# motor.net
KiCad netlist of a schematic drawn in EAGLE
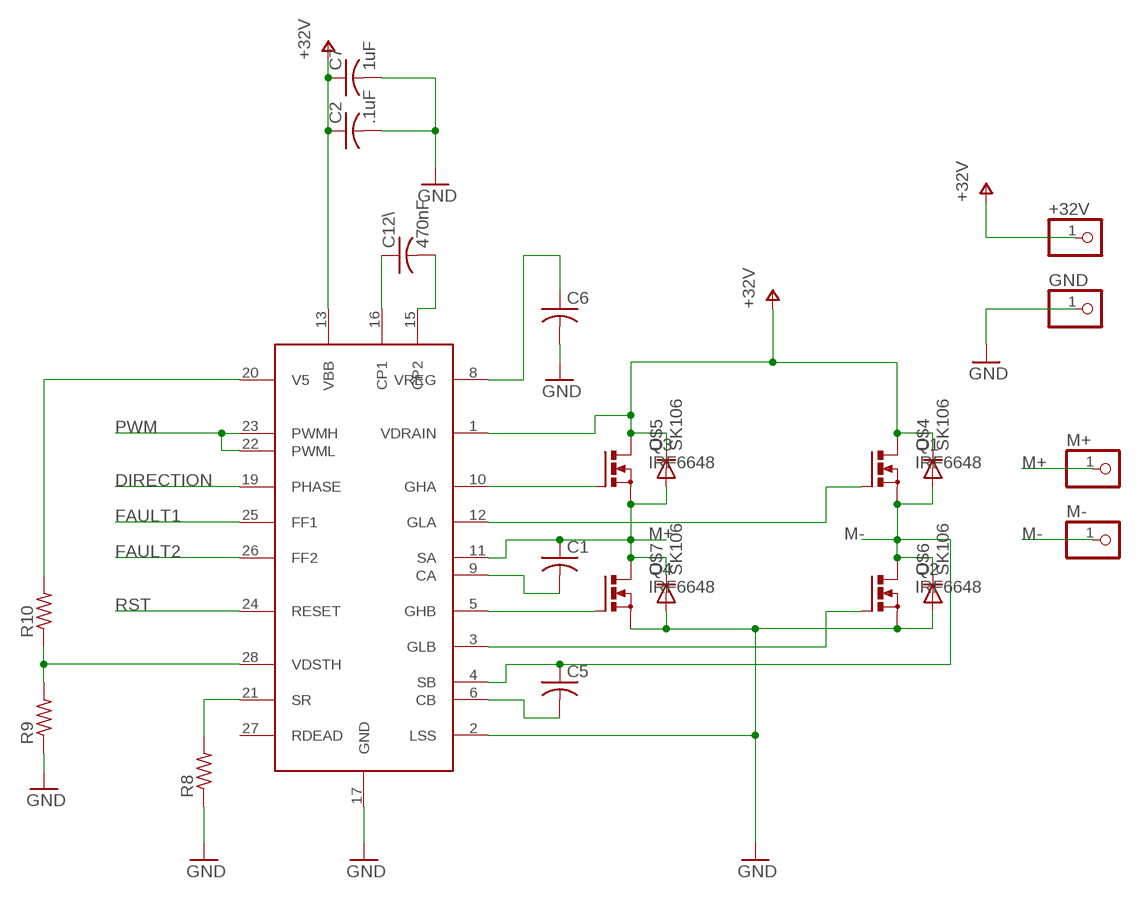
[diagram p0: schematic, sheet 1]
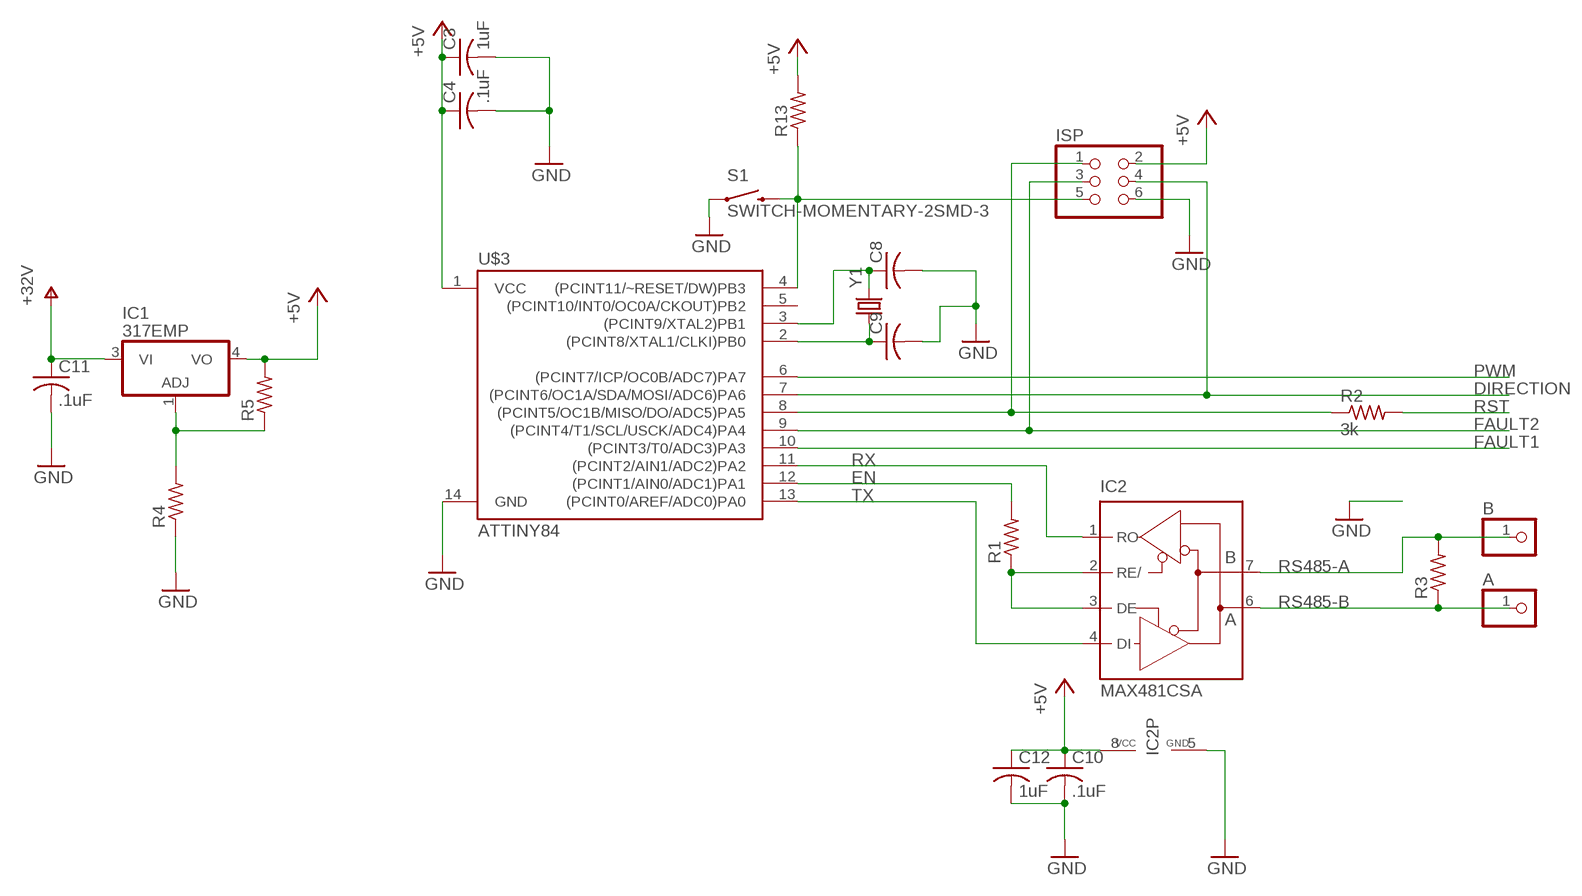
[diagram p1: schematic, sheet 2]

(export (version "E")
  (design (tool "Eeschema 10.0.6"))
  (components
    (comp (ref "A")
      (value "PINHD-1X1")
      (footprint "eagle-import:1X01")
      (libsource (lib "eagle-import") (part "PINHD-1X1"))
    )
    (comp (ref "B")
      (value "PINHD-1X1")
      (footprint "eagle-import:1X01")
      (libsource (lib "eagle-import") (part "PINHD-1X1"))
    )
    (comp (ref "C3")
      (value "1uF")
      (footprint "eagle-import:C0603")
      (libsource (lib "eagle-import") (part "C-USC0603"))
    )
    (comp (ref "C4")
      (value ".1uF")
      (footprint "eagle-import:C0603")
      (libsource (lib "eagle-import") (part "C-USC0603"))
    )
    (comp (ref "C8")
      (value "C-USC0603")
      (footprint "eagle-import:C0603")
      (libsource (lib "eagle-import") (part "C-USC0603"))
    )
    (comp (ref "C9")
      (value "C-USC0603")
      (footprint "eagle-import:C0603")
      (libsource (lib "eagle-import") (part "C-USC0603"))
    )
    (comp (ref "C10")
      (value ".1uF")
      (footprint "eagle-import:C0603")
      (libsource (lib "eagle-import") (part "C-USC0603"))
    )
    (comp (ref "C11")
      (value ".1uF")
      (footprint "eagle-import:C0603")
      (libsource (lib "eagle-import") (part "C-USC0603"))
    )
    (comp (ref "C12")
      (value "1uF")
      (footprint "eagle-import:C0603")
      (libsource (lib "eagle-import") (part "C-USC0603"))
    )
    (comp (ref "IC1")
      (value "317EMP")
      (footprint "eagle-import:SOT223")
      (libsource (lib "eagle-import") (part "317EMP"))
    )
    (comp (ref "IC2")
      (value "MAX481CSA")
      (footprint "eagle-import:SO08")
      (fields (field (name "MF") "MAXIM"))
      (libsource (lib "eagle-import") (part "MAX481CSA"))
    )
    (comp (ref "ISP")
      (value "PINHD-2X3")
      (footprint "eagle-import:2X03")
      (libsource (lib "eagle-import") (part "PINHD-2X3"))
    )
    (comp (ref "R1")
      (value "R-US_R0603")
      (footprint "eagle-import:R0603")
      (libsource (lib "eagle-import") (part "R-US_R0603"))
    )
    (comp (ref "R2")
      (value "3k")
      (footprint "eagle-import:R0603")
      (libsource (lib "eagle-import") (part "R-US_R0603"))
    )
    (comp (ref "R3")
      (value "R-US_R0603")
      (footprint "eagle-import:R0603")
      (libsource (lib "eagle-import") (part "R-US_R0603"))
    )
    (comp (ref "R4")
      (value "R-US_R0603")
      (footprint "eagle-import:R0603")
      (libsource (lib "eagle-import") (part "R-US_R0603"))
    )
    (comp (ref "R5")
      (value "R-US_R0603")
      (footprint "eagle-import:R0603")
      (libsource (lib "eagle-import") (part "R-US_R0603"))
    )
    (comp (ref "R13")
      (value "R-US_R0603")
      (footprint "eagle-import:R0603")
      (libsource (lib "eagle-import") (part "R-US_R0603"))
    )
    (comp (ref "S1")
      (value "SWITCH-MOMENTARY-2SMD-3")
      (footprint "eagle-import:TACTILE_SWITCH_SMD-3")
      (libsource (lib "eagle-import") (part "SWITCH-MOMENTARY-2SMD-3"))
    )
    (comp (ref "U$3")
      (value "ATTINY84")
      (footprint "eagle-import:SO14")
      (libsource (lib "eagle-import") (part "ATTINY84"))
    )
    (comp (ref "Y1")
      (value "CRYSTAL")
      (footprint "eagle-import:MYSMD2_RESONATOR")
      (libsource (lib "eagle-import") (part "CRYSTAL"))
    )
    (comp (ref "+32V")
      (value "PINHD-1X1")
      (footprint "eagle-import:1X01")
      (libsource (lib "eagle-import") (part "PINHD-1X1"))
    )
    (comp (ref "C1")
      (value "C-USC0603")
      (footprint "eagle-import:C0603")
      (libsource (lib "eagle-import") (part "C-USC0603"))
    )
    (comp (ref "C2")
      (value ".1uF")
      (footprint "eagle-import:C0603")
      (libsource (lib "eagle-import") (part "C-USC0603"))
    )
    (comp (ref "C5")
      (value "C-USC0603")
      (footprint "eagle-import:C0603")
      (libsource (lib "eagle-import") (part "C-USC0603"))
    )
    (comp (ref "C6")
      (value "C-USC0603")
      (footprint "eagle-import:C0603")
      (libsource (lib "eagle-import") (part "C-USC0603"))
    )
    (comp (ref "C7")
      (value "1uF")
      (footprint "eagle-import:C0603")
      (libsource (lib "eagle-import") (part "C-USC0603"))
    )
    (comp (ref "C12\\")
      (value "470nF")
      (footprint "eagle-import:C0603")
      (libsource (lib "eagle-import") (part "C-USC0603"))
    )
    (comp (ref "GND")
      (value "PINHD-1X1")
      (footprint "eagle-import:1X01")
      (libsource (lib "eagle-import") (part "PINHD-1X1"))
    )
    (comp (ref "M+")
      (value "PINHD-1X1")
      (footprint "eagle-import:1X01")
      (libsource (lib "eagle-import") (part "PINHD-1X1"))
    )
    (comp (ref "M-")
      (value "PINHD-1X1")
      (footprint "eagle-import:1X01")
      (libsource (lib "eagle-import") (part "PINHD-1X1"))
    )
    (comp (ref "Q1")
      (value "IRF6648")
      (footprint "eagle-import:DIRECTFET")
      (libsource (lib "eagle-import") (part "IRF6648"))
    )
    (comp (ref "Q2")
      (value "IRF6648")
      (footprint "eagle-import:DIRECTFET")
      (libsource (lib "eagle-import") (part "IRF6648"))
    )
    (comp (ref "Q3")
      (value "IRF6648")
      (footprint "eagle-import:DIRECTFET")
      (libsource (lib "eagle-import") (part "IRF6648"))
    )
    (comp (ref "Q4")
      (value "IRF6648")
      (footprint "eagle-import:DIRECTFET")
      (libsource (lib "eagle-import") (part "IRF6648"))
    )
    (comp (ref "R8")
      (value "R-US_R0603")
      (footprint "eagle-import:R0603")
      (libsource (lib "eagle-import") (part "R-US_R0603"))
    )
    (comp (ref "R9")
      (value "R-US_R0603")
      (footprint "eagle-import:R0603")
      (libsource (lib "eagle-import") (part "R-US_R0603"))
    )
    (comp (ref "R10")
      (value "R-US_R0603")
      (footprint "eagle-import:R0603")
      (libsource (lib "eagle-import") (part "R-US_R0603"))
    )
    (comp (ref "U$1")
      (value "ALLEGRO-A3921")
      (footprint "eagle-import:TSSOP28")
      (libsource (lib "eagle-import") (part "ALLEGRO-A3921"))
    )
    (comp (ref "U$4")
      (value "SK106")
      (footprint "eagle-import:DO-214AB")
      (libsource (lib "eagle-import") (part "SK106"))
    )
    (comp (ref "U$5")
      (value "SK106")
      (footprint "eagle-import:DO-214AB")
      (libsource (lib "eagle-import") (part "SK106"))
    )
    (comp (ref "U$6")
      (value "SK106")
      (footprint "eagle-import:DO-214AB")
      (libsource (lib "eagle-import") (part "SK106"))
    )
    (comp (ref "U$7")
      (value "SK106")
      (footprint "eagle-import:DO-214AB")
      (libsource (lib "eagle-import") (part "SK106"))
    )
  )
  (nets
    (net (code "1") (name "+5V") (class "Default")
      (node (ref "C10") (pin "1") (pinfunction "1_1") (pintype "passive"))
      (node (ref "C12") (pin "1") (pinfunction "1_1") (pintype "passive"))
      (node (ref "C3") (pin "1") (pinfunction "1_1") (pintype "passive"))
      (node (ref "C4") (pin "1") (pinfunction "1_1") (pintype "passive"))
      (node (ref "IC1") (pin "4") (pinfunction "VO_4") (pintype "passive"))
      (node (ref "IC2") (pin "8") (pinfunction "VCC_8") (pintype "power_in"))
      (node (ref "ISP") (pin "2") (pinfunction "2_2") (pintype "passive"))
      (node (ref "R13") (pin "2") (pinfunction "2_2") (pintype "passive"))
      (node (ref "R5") (pin "2") (pinfunction "2_2") (pintype "passive"))
      (node (ref "U$3") (pin "1") (pinfunction "VCC_1") (pintype "bidirectional"))
    )
    (net (code "2") (name "+32V") (class "Default")
      (node (ref "+32V") (pin "1") (pinfunction "1_1") (pintype "passive"))
      (node (ref "C11") (pin "1") (pinfunction "1_1") (pintype "passive"))
      (node (ref "C2") (pin "1") (pinfunction "1_1") (pintype "passive"))
      (node (ref "C7") (pin "1") (pinfunction "1_1") (pintype "passive"))
      (node (ref "IC1") (pin "3") (pinfunction "VI_3") (pintype "input"))
      (node (ref "Q1") (pin "D@1") (pinfunction "D_D@1") (pintype "passive"))
      (node (ref "Q1") (pin "D@2") (pinfunction "D_D@2") (pintype "passive"))
      (node (ref "Q1") (pin "D@3") (pinfunction "D_D@3") (pintype "passive"))
      (node (ref "Q1") (pin "D@4") (pinfunction "D_D@4") (pintype "passive"))
      (node (ref "Q3") (pin "D@1") (pinfunction "D_D@1") (pintype "passive"))
      (node (ref "Q3") (pin "D@2") (pinfunction "D_D@2") (pintype "passive"))
      (node (ref "Q3") (pin "D@3") (pinfunction "D_D@3") (pintype "passive"))
      (node (ref "Q3") (pin "D@4") (pinfunction "D_D@4") (pintype "passive"))
      (node (ref "U$1") (pin "1") (pinfunction "VDRAIN_1") (pintype "bidirectional"))
      (node (ref "U$1") (pin "13") (pinfunction "VBB_13") (pintype "bidirectional"))
      (node (ref "U$4") (pin "P$2") (pinfunction "C_P$2") (pintype "passive"))
      (node (ref "U$5") (pin "P$2") (pinfunction "C_P$2") (pintype "passive"))
    )
    (net (code "3") (name "DIRECTION") (class "Default")
      (node (ref "ISP") (pin "4") (pinfunction "4_4") (pintype "passive"))
      (node (ref "U$1") (pin "19") (pinfunction "PHASE_19") (pintype "bidirectional"))
      (node (ref "U$3") (pin "7") (pinfunction "(PCINT6/OC1A/SDA/MOSI/ADC6)PA6_7") (pintype "bidirectional"))
    )
    (net (code "4") (name "EN") (class "Default")
      (node (ref "R1") (pin "2") (pinfunction "2_2") (pintype "passive"))
      (node (ref "U$3") (pin "12") (pinfunction "(PCINT1/AIN0/ADC1)PA1_12") (pintype "bidirectional"))
    )
    (net (code "5") (name "FAULT1") (class "Default")
      (node (ref "U$1") (pin "25") (pinfunction "FF1_25") (pintype "bidirectional"))
      (node (ref "U$3") (pin "10") (pinfunction "(PCINT3/T0/ADC3)PA3_10") (pintype "bidirectional"))
    )
    (net (code "6") (name "FAULT2") (class "Default")
      (node (ref "ISP") (pin "3") (pinfunction "3_3") (pintype "passive"))
      (node (ref "U$1") (pin "26") (pinfunction "FF2_26") (pintype "bidirectional"))
      (node (ref "U$3") (pin "9") (pinfunction "(PCINT4/T1/SCL/USCK/ADC4)PA4_9") (pintype "bidirectional"))
    )
    (net (code "7") (name "GND") (class "Default")
      (node (ref "C10") (pin "2") (pinfunction "2_2") (pintype "passive"))
      (node (ref "C11") (pin "2") (pinfunction "2_2") (pintype "passive"))
      (node (ref "C12") (pin "2") (pinfunction "2_2") (pintype "passive"))
      (node (ref "C2") (pin "2") (pinfunction "2_2") (pintype "passive"))
      (node (ref "C3") (pin "2") (pinfunction "2_2") (pintype "passive"))
      (node (ref "C4") (pin "2") (pinfunction "2_2") (pintype "passive"))
      (node (ref "C6") (pin "2") (pinfunction "2_2") (pintype "passive"))
      (node (ref "C7") (pin "2") (pinfunction "2_2") (pintype "passive"))
      (node (ref "C8") (pin "2") (pinfunction "2_2") (pintype "passive"))
      (node (ref "C9") (pin "2") (pinfunction "2_2") (pintype "passive"))
      (node (ref "GND") (pin "1") (pinfunction "1_1") (pintype "passive"))
      (node (ref "IC2") (pin "5") (pinfunction "GND_5") (pintype "power_in"))
      (node (ref "ISP") (pin "6") (pinfunction "6_6") (pintype "passive"))
      (node (ref "Q2") (pin "S@1") (pinfunction "S_S@1") (pintype "passive"))
      (node (ref "Q2") (pin "S@2") (pinfunction "S_S@2") (pintype "passive"))
      (node (ref "Q4") (pin "S@1") (pinfunction "S_S@1") (pintype "passive"))
      (node (ref "Q4") (pin "S@2") (pinfunction "S_S@2") (pintype "passive"))
      (node (ref "R4") (pin "1") (pinfunction "1_1") (pintype "passive"))
      (node (ref "R8") (pin "1") (pinfunction "1_1") (pintype "passive"))
      (node (ref "R9") (pin "1") (pinfunction "1_1") (pintype "passive"))
      (node (ref "S1") (pin "1") (pinfunction "1_1") (pintype "passive"))
      (node (ref "U$1") (pin "17") (pinfunction "GND_17") (pintype "bidirectional"))
      (node (ref "U$1") (pin "2") (pinfunction "LSS_2") (pintype "bidirectional"))
      (node (ref "U$3") (pin "14") (pinfunction "GND_14") (pintype "bidirectional"))
      (node (ref "U$6") (pin "P$1") (pinfunction "A_P$1") (pintype "passive"))
      (node (ref "U$7") (pin "P$1") (pinfunction "A_P$1") (pintype "passive"))
    )
    (net (code "8") (name "M+") (class "Default")
      (node (ref "C1") (pin "1") (pinfunction "1_1") (pintype "passive"))
      (node (ref "M+") (pin "1") (pinfunction "1_1") (pintype "passive"))
      (node (ref "Q3") (pin "S@1") (pinfunction "S_S@1") (pintype "passive"))
      (node (ref "Q3") (pin "S@2") (pinfunction "S_S@2") (pintype "passive"))
      (node (ref "Q4") (pin "D@1") (pinfunction "D_D@1") (pintype "passive"))
      (node (ref "Q4") (pin "D@2") (pinfunction "D_D@2") (pintype "passive"))
      (node (ref "Q4") (pin "D@3") (pinfunction "D_D@3") (pintype "passive"))
      (node (ref "Q4") (pin "D@4") (pinfunction "D_D@4") (pintype "passive"))
      (node (ref "U$1") (pin "11") (pinfunction "SA_11") (pintype "bidirectional"))
      (node (ref "U$5") (pin "P$1") (pinfunction "A_P$1") (pintype "passive"))
      (node (ref "U$7") (pin "P$2") (pinfunction "C_P$2") (pintype "passive"))
    )
    (net (code "9") (name "M-") (class "Default")
      (node (ref "C5") (pin "1") (pinfunction "1_1") (pintype "passive"))
      (node (ref "M-") (pin "1") (pinfunction "1_1") (pintype "passive"))
      (node (ref "Q1") (pin "S@1") (pinfunction "S_S@1") (pintype "passive"))
      (node (ref "Q1") (pin "S@2") (pinfunction "S_S@2") (pintype "passive"))
      (node (ref "Q2") (pin "D@1") (pinfunction "D_D@1") (pintype "passive"))
      (node (ref "Q2") (pin "D@2") (pinfunction "D_D@2") (pintype "passive"))
      (node (ref "Q2") (pin "D@3") (pinfunction "D_D@3") (pintype "passive"))
      (node (ref "Q2") (pin "D@4") (pinfunction "D_D@4") (pintype "passive"))
      (node (ref "U$1") (pin "4") (pinfunction "SB_4") (pintype "bidirectional"))
      (node (ref "U$4") (pin "P$1") (pinfunction "A_P$1") (pintype "passive"))
      (node (ref "U$6") (pin "P$2") (pinfunction "C_P$2") (pintype "passive"))
    )
    (net (code "10") (name "Net-(IC1-ADJ)") (class "Default")
      (node (ref "IC1") (pin "1") (pinfunction "ADJ_1") (pintype "input"))
      (node (ref "R4") (pin "2") (pinfunction "2_2") (pintype "passive"))
      (node (ref "R5") (pin "1") (pinfunction "1_1") (pintype "passive"))
    )
    (net (code "11") (name "Net-(IC2A-DE)") (class "Default")
      (node (ref "IC2") (pin "2") (pinfunction "RE/_2") (pintype "input"))
      (node (ref "IC2") (pin "3") (pinfunction "DE_3") (pintype "input"))
      (node (ref "R1") (pin "1") (pinfunction "1_1") (pintype "passive"))
    )
    (net (code "12") (name "Net-(S1-2)") (class "Default")
      (node (ref "ISP") (pin "5") (pinfunction "5_5") (pintype "passive"))
      (node (ref "R13") (pin "1") (pinfunction "1_1") (pintype "passive"))
      (node (ref "S1") (pin "4") (pinfunction "2_4") (pintype "passive"))
      (node (ref "U$3") (pin "4") (pinfunction "(PCINT11/~{RESET/DW})PB3_4") (pintype "bidirectional"))
    )
    (net (code "13") (name "Net-(U$1-CA)") (class "Default")
      (node (ref "C1") (pin "2") (pinfunction "2_2") (pintype "passive"))
      (node (ref "U$1") (pin "9") (pinfunction "CA_9") (pintype "bidirectional"))
    )
    (net (code "14") (name "Net-(U$1-CB)") (class "Default")
      (node (ref "C5") (pin "2") (pinfunction "2_2") (pintype "passive"))
      (node (ref "U$1") (pin "6") (pinfunction "CB_6") (pintype "bidirectional"))
    )
    (net (code "15") (name "Net-(U$1-CP1)") (class "Default")
      (node (ref "C12\\") (pin "1") (pinfunction "1_1") (pintype "passive"))
      (node (ref "U$1") (pin "16") (pinfunction "CP1_16") (pintype "bidirectional"))
    )
    (net (code "16") (name "Net-(U$1-CP2)") (class "Default")
      (node (ref "C12\\") (pin "2") (pinfunction "2_2") (pintype "passive"))
      (node (ref "U$1") (pin "15") (pinfunction "CP2_15") (pintype "bidirectional"))
    )
    (net (code "17") (name "Net-(U$1-GHA)") (class "Default")
      (node (ref "Q3") (pin "G") (pinfunction "G_G") (pintype "passive"))
      (node (ref "U$1") (pin "10") (pinfunction "GHA_10") (pintype "bidirectional"))
    )
    (net (code "18") (name "Net-(U$1-GHB)") (class "Default")
      (node (ref "Q4") (pin "G") (pinfunction "G_G") (pintype "passive"))
      (node (ref "U$1") (pin "5") (pinfunction "GHB_5") (pintype "bidirectional"))
    )
    (net (code "19") (name "Net-(U$1-GLA)") (class "Default")
      (node (ref "Q1") (pin "G") (pinfunction "G_G") (pintype "passive"))
      (node (ref "U$1") (pin "12") (pinfunction "GLA_12") (pintype "bidirectional"))
    )
    (net (code "20") (name "Net-(U$1-GLB)") (class "Default")
      (node (ref "Q2") (pin "G") (pinfunction "G_G") (pintype "passive"))
      (node (ref "U$1") (pin "3") (pinfunction "GLB_3") (pintype "bidirectional"))
    )
    (net (code "21") (name "Net-(U$1-SR)") (class "Default")
      (node (ref "R8") (pin "2") (pinfunction "2_2") (pintype "passive"))
      (node (ref "U$1") (pin "21") (pinfunction "SR_21") (pintype "bidirectional"))
    )
    (net (code "22") (name "Net-(U$1-V5)") (class "Default")
      (node (ref "R10") (pin "2") (pinfunction "2_2") (pintype "passive"))
      (node (ref "U$1") (pin "20") (pinfunction "V5_20") (pintype "bidirectional"))
    )
    (net (code "23") (name "Net-(U$1-VDSTH)") (class "Default")
      (node (ref "R10") (pin "1") (pinfunction "1_1") (pintype "passive"))
      (node (ref "R9") (pin "2") (pinfunction "2_2") (pintype "passive"))
      (node (ref "U$1") (pin "28") (pinfunction "VDSTH_28") (pintype "bidirectional"))
    )
    (net (code "24") (name "Net-(U$1-VREG)") (class "Default")
      (node (ref "C6") (pin "1") (pinfunction "1_1") (pintype "passive"))
      (node (ref "U$1") (pin "8") (pinfunction "VREG_8") (pintype "bidirectional"))
    )
    (net (code "25") (name "Net-(U$3-(PCINT5{slash}OC1B{slash}MISO{slash}DO{slash}ADC5)PA5)") (class "Default")
      (node (ref "ISP") (pin "1") (pinfunction "1_1") (pintype "passive"))
      (node (ref "R2") (pin "1") (pinfunction "1_1") (pintype "passive"))
      (node (ref "U$3") (pin "8") (pinfunction "(PCINT5/OC1B/MISO/DO/ADC5)PA5_8") (pintype "bidirectional"))
    )
    (net (code "26") (name "Net-(U$3-(PCINT8{slash}XTAL1{slash}CLKI)PB0)") (class "Default")
      (node (ref "C9") (pin "1") (pinfunction "1_1") (pintype "passive"))
      (node (ref "U$3") (pin "2") (pinfunction "(PCINT8/XTAL1/CLKI)PB0_2") (pintype "bidirectional"))
      (node (ref "Y1") (pin "1") (pinfunction "1_1") (pintype "passive"))
    )
    (net (code "27") (name "Net-(U$3-(PCINT9{slash}XTAL2)PB1)") (class "Default")
      (node (ref "C8") (pin "1") (pinfunction "1_1") (pintype "passive"))
      (node (ref "U$3") (pin "3") (pinfunction "(PCINT9/XTAL2)PB1_3") (pintype "bidirectional"))
      (node (ref "Y1") (pin "3") (pinfunction "2_3") (pintype "passive"))
    )
    (net (code "28") (name "PWM") (class "Default")
      (node (ref "U$1") (pin "22") (pinfunction "PWML_22") (pintype "bidirectional"))
      (node (ref "U$1") (pin "23") (pinfunction "PWMH_23") (pintype "bidirectional"))
      (node (ref "U$3") (pin "6") (pinfunction "(PCINT7/ICP/OC0B/ADC7)PA7_6") (pintype "bidirectional"))
    )
    (net (code "29") (name "RS485-A") (class "Default")
      (node (ref "B") (pin "1") (pinfunction "1_1") (pintype "passive"))
      (node (ref "IC2") (pin "7") (pinfunction "B_7") (pintype "passive"))
      (node (ref "R3") (pin "2") (pinfunction "2_2") (pintype "passive"))
    )
    (net (code "30") (name "RS485-B") (class "Default")
      (node (ref "A") (pin "1") (pinfunction "1_1") (pintype "passive"))
      (node (ref "IC2") (pin "6") (pinfunction "A_6") (pintype "passive"))
      (node (ref "R3") (pin "1") (pinfunction "1_1") (pintype "passive"))
    )
    (net (code "31") (name "RST") (class "Default")
      (node (ref "R2") (pin "2") (pinfunction "2_2") (pintype "passive"))
      (node (ref "U$1") (pin "24") (pinfunction "RESET_24") (pintype "bidirectional"))
    )
    (net (code "32") (name "RX") (class "Default")
      (node (ref "IC2") (pin "1") (pinfunction "RO_1") (pintype "output"))
      (node (ref "U$3") (pin "11") (pinfunction "(PCINT2/AIN1/ADC2)PA2_11") (pintype "bidirectional"))
    )
    (net (code "33") (name "TX") (class "Default")
      (node (ref "IC2") (pin "4") (pinfunction "DI_4") (pintype "input"))
      (node (ref "U$3") (pin "13") (pinfunction "(PCINT0/AREF/ADC0)PA0_13") (pintype "bidirectional"))
    )
    (net (code "34") (name "unconnected-(U$1-RDEAD-Pad27)") (class "Default")
      (node (ref "U$1") (pin "27") (pinfunction "RDEAD_27") (pintype "bidirectional"))
    )
    (net (code "35") (name "unconnected-(U$3-(PCINT10{slash}INT0{slash}OC0A{slash}CKOUT)PB2-Pad5)") (class "Default")
      (node (ref "U$3") (pin "5") (pinfunction "(PCINT10/INT0/OC0A/CKOUT)PB2_5") (pintype "bidirectional"))
    )
  )
)
